# Triple_Socket.net
KiCad netlist of a schematic drawn in EAGLE
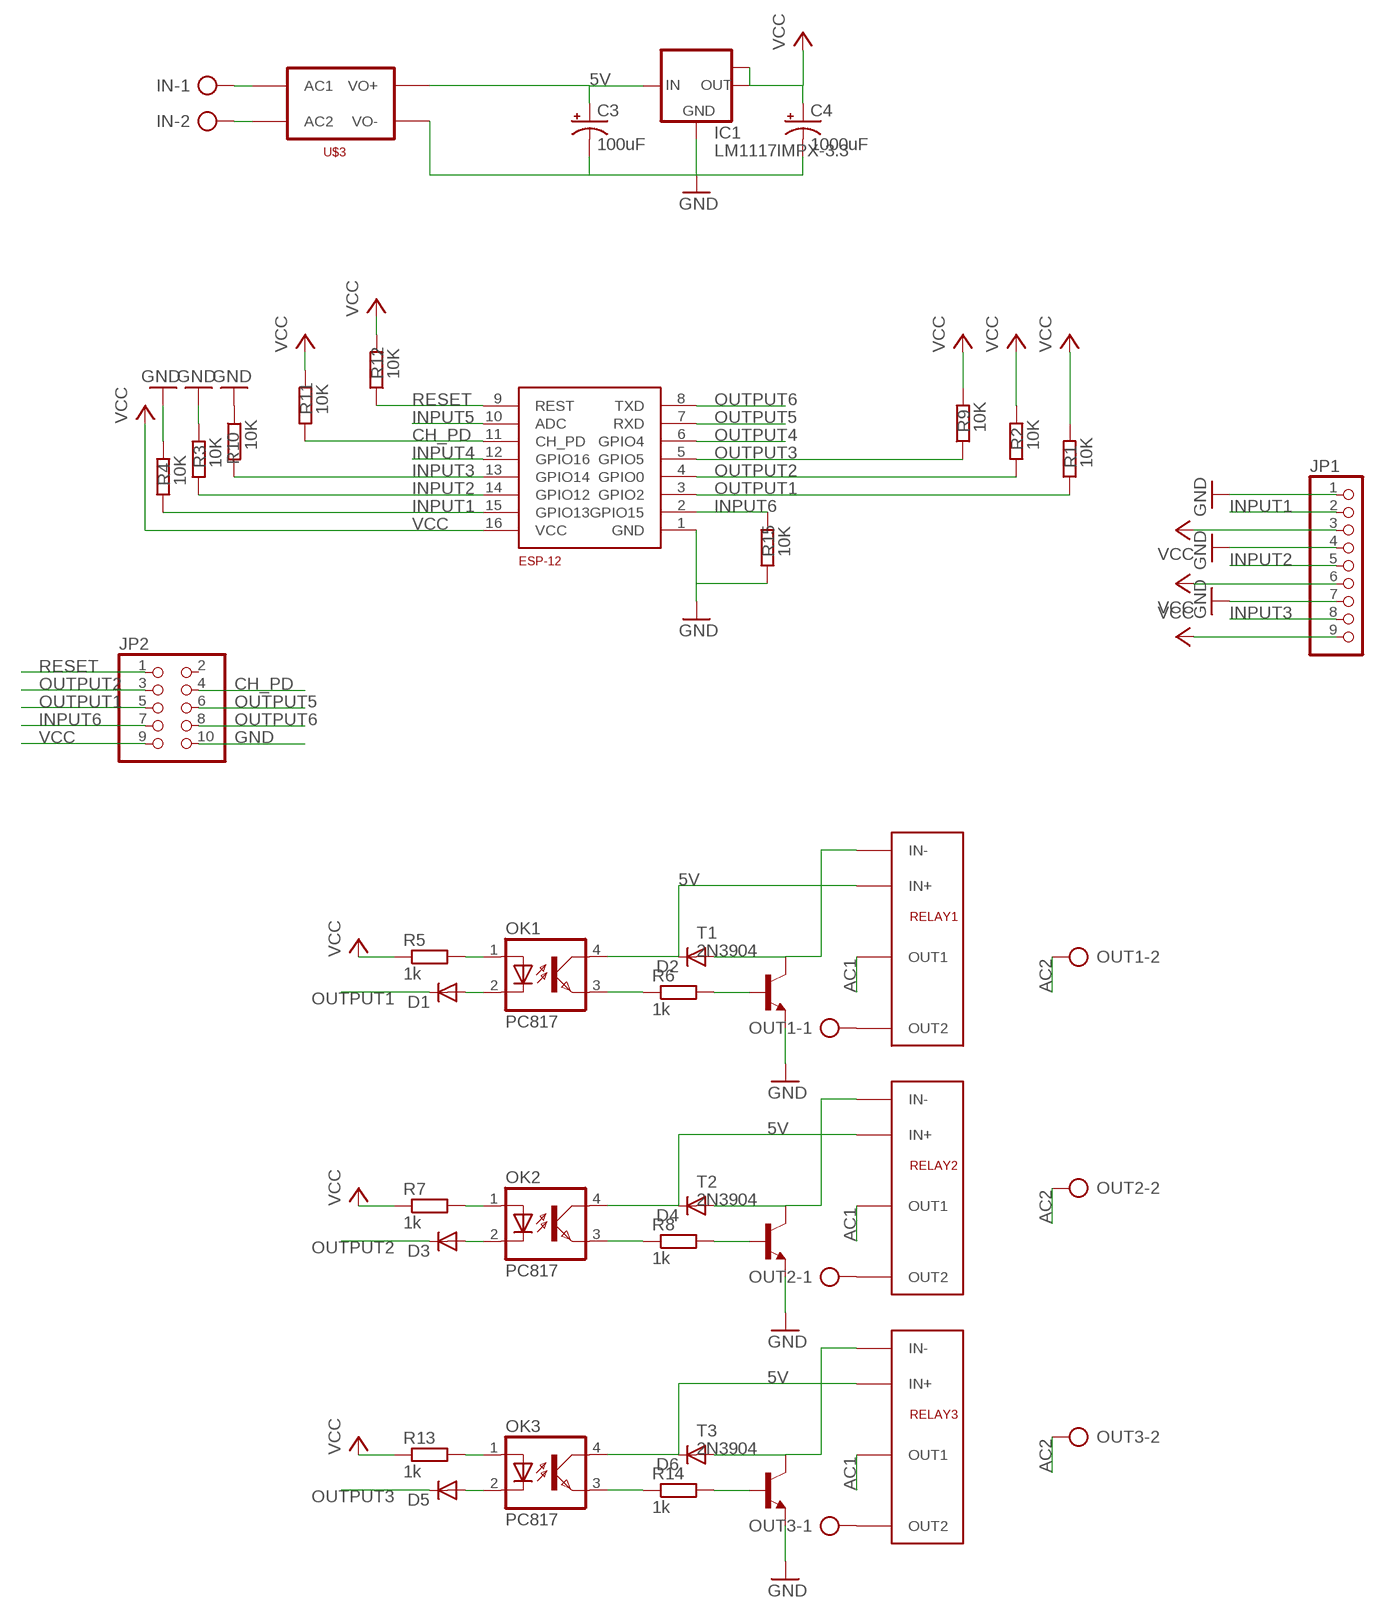
[diagram p0: schematic, sheet 1]

(export (version "E")
  (design (tool "Eeschema 10.0.6"))
  (components
    (comp (ref "C3")
      (value "100uF")
      (footprint "eagle-import:E5-10,5")
      (libsource (lib "eagle-import") (part "CPOL-USE5-10.5"))
    )
    (comp (ref "C4")
      (value "1000uF")
      (footprint "eagle-import:E5-10,5")
      (libsource (lib "eagle-import") (part "CPOL-USE5-10.5"))
    )
    (comp (ref "D1")
      (value "DIODE-SOD80C")
      (footprint "eagle-import:SOD80C")
      (libsource (lib "eagle-import") (part "DIODE-SOD80C"))
    )
    (comp (ref "D2")
      (value "DIODE-SOD80C")
      (footprint "eagle-import:SOD80C")
      (libsource (lib "eagle-import") (part "DIODE-SOD80C"))
    )
    (comp (ref "D3")
      (value "DIODE-SOD80C")
      (footprint "eagle-import:SOD80C")
      (libsource (lib "eagle-import") (part "DIODE-SOD80C"))
    )
    (comp (ref "D4")
      (value "DIODE-SOD80C")
      (footprint "eagle-import:SOD80C")
      (libsource (lib "eagle-import") (part "DIODE-SOD80C"))
    )
    (comp (ref "D5")
      (value "DIODE-SOD80C")
      (footprint "eagle-import:SOD80C")
      (libsource (lib "eagle-import") (part "DIODE-SOD80C"))
    )
    (comp (ref "D6")
      (value "DIODE-SOD80C")
      (footprint "eagle-import:SOD80C")
      (libsource (lib "eagle-import") (part "DIODE-SOD80C"))
    )
    (comp (ref "ESP-12")
      (value "ESP8266_ESP-12")
      (footprint "eagle-import:ESP8266-ESP12")
      (libsource (lib "eagle-import") (part "ESP8266_ESP-12"))
    )
    (comp (ref "IC1")
      (value "LM1117IMPX-3.3")
      (footprint "eagle-import:SOT223")
      (libsource (lib "eagle-import") (part "LM1117IMPX-3.3"))
    )
    (comp (ref "IN")
      (value "AK500/2-H")
      (footprint "eagle-import:AK500_2-H")
      (libsource (lib "eagle-import") (part "AK500/2-H"))
    )
    (comp (ref "JP1")
      (value "PINHD-1X9")
      (footprint "eagle-import:1X09")
      (libsource (lib "eagle-import") (part "PINHD-1X9"))
    )
    (comp (ref "JP2")
      (value "PINHD-2X5")
      (footprint "eagle-import:2X05")
      (libsource (lib "eagle-import") (part "PINHD-2X5"))
    )
    (comp (ref "OK1")
      (value "PC817")
      (footprint "eagle-import:DIL04")
      (fields (field (name "MPN") "PC817X4J000F"))
      (libsource (lib "eagle-import") (part "PC817"))
    )
    (comp (ref "OK2")
      (value "PC817")
      (footprint "eagle-import:DIL04")
      (fields (field (name "MPN") "PC817X4J000F"))
      (libsource (lib "eagle-import") (part "PC817"))
    )
    (comp (ref "OK3")
      (value "PC817")
      (footprint "eagle-import:DIL04")
      (fields (field (name "MPN") "PC817X4J000F"))
      (libsource (lib "eagle-import") (part "PC817"))
    )
    (comp (ref "OUT1")
      (value "AK500/2-H")
      (footprint "eagle-import:AK500_2-H")
      (libsource (lib "eagle-import") (part "AK500/2-H"))
    )
    (comp (ref "OUT2")
      (value "AK500/2-H")
      (footprint "eagle-import:AK500_2-H")
      (libsource (lib "eagle-import") (part "AK500/2-H"))
    )
    (comp (ref "OUT3")
      (value "AK500/2-H")
      (footprint "eagle-import:AK500_2-H")
      (libsource (lib "eagle-import") (part "AK500/2-H"))
    )
    (comp (ref "R1")
      (value "10K")
      (footprint "eagle-import:R0805")
      (libsource (lib "eagle-import") (part "R-EU_R0805"))
    )
    (comp (ref "R2")
      (value "10K")
      (footprint "eagle-import:R0805")
      (libsource (lib "eagle-import") (part "R-EU_R0805"))
    )
    (comp (ref "R3")
      (value "10K")
      (footprint "eagle-import:R0805")
      (libsource (lib "eagle-import") (part "R-EU_R0805"))
    )
    (comp (ref "R4")
      (value "10K")
      (footprint "eagle-import:R0805")
      (libsource (lib "eagle-import") (part "R-EU_R0805"))
    )
    (comp (ref "R5")
      (value "1k")
      (footprint "eagle-import:R0805")
      (libsource (lib "eagle-import") (part "R-EU_R0805"))
    )
    (comp (ref "R6")
      (value "1k")
      (footprint "eagle-import:R0805")
      (libsource (lib "eagle-import") (part "R-EU_R0805"))
    )
    (comp (ref "R7")
      (value "1k")
      (footprint "eagle-import:R0805")
      (libsource (lib "eagle-import") (part "R-EU_R0805"))
    )
    (comp (ref "R8")
      (value "1k")
      (footprint "eagle-import:R0805")
      (libsource (lib "eagle-import") (part "R-EU_R0805"))
    )
    (comp (ref "R9")
      (value "10K")
      (footprint "eagle-import:R0805")
      (libsource (lib "eagle-import") (part "R-EU_R0805"))
    )
    (comp (ref "R10")
      (value "10K")
      (footprint "eagle-import:R0805")
      (libsource (lib "eagle-import") (part "R-EU_R0805"))
    )
    (comp (ref "R11")
      (value "10K")
      (footprint "eagle-import:R0805")
      (libsource (lib "eagle-import") (part "R-EU_R0805"))
    )
    (comp (ref "R12")
      (value "10K")
      (footprint "eagle-import:R0805")
      (libsource (lib "eagle-import") (part "R-EU_R0805"))
    )
    (comp (ref "R13")
      (value "1k")
      (footprint "eagle-import:R0805")
      (libsource (lib "eagle-import") (part "R-EU_R0805"))
    )
    (comp (ref "R14")
      (value "1k")
      (footprint "eagle-import:R0805")
      (libsource (lib "eagle-import") (part "R-EU_R0805"))
    )
    (comp (ref "R15")
      (value "10K")
      (footprint "eagle-import:R0805")
      (libsource (lib "eagle-import") (part "R-EU_R0805"))
    )
    (comp (ref "RELAY1")
      (value "G3MB-202P")
      (footprint "eagle-import:G3MB-202P")
      (libsource (lib "eagle-import") (part "G3MB-202P"))
    )
    (comp (ref "RELAY2")
      (value "G3MB-202P")
      (footprint "eagle-import:G3MB-202P")
      (libsource (lib "eagle-import") (part "G3MB-202P"))
    )
    (comp (ref "RELAY3")
      (value "G3MB-202P")
      (footprint "eagle-import:G3MB-202P")
      (libsource (lib "eagle-import") (part "G3MB-202P"))
    )
    (comp (ref "T1")
      (value "2N3904")
      (footprint "eagle-import:TO92")
      (libsource (lib "eagle-import") (part "2N3904"))
    )
    (comp (ref "T2")
      (value "2N3904")
      (footprint "eagle-import:TO92")
      (libsource (lib "eagle-import") (part "2N3904"))
    )
    (comp (ref "T3")
      (value "2N3904")
      (footprint "eagle-import:TO92")
      (libsource (lib "eagle-import") (part "2N3904"))
    )
    (comp (ref "U$3")
      (value "HLK-PM01")
      (footprint "eagle-import:HLK-PM01")
      (libsource (lib "eagle-import") (part "HLK-PM01"))
    )
  )
  (nets
    (net (code "1") (name "/5V") (class "Default")
      (node (ref "C3") (pin "+") (pinfunction "+_+") (pintype "passive"))
      (node (ref "D2") (pin "C") (pinfunction "C_C") (pintype "passive"))
      (node (ref "D4") (pin "C") (pinfunction "C_C") (pintype "passive"))
      (node (ref "D6") (pin "C") (pinfunction "C_C") (pintype "passive"))
      (node (ref "IC1") (pin "3") (pinfunction "IN_3") (pintype "input"))
      (node (ref "OK1") (pin "4") (pinfunction "COL_4") (pintype "passive"))
      (node (ref "OK2") (pin "4") (pinfunction "COL_4") (pintype "passive"))
      (node (ref "OK3") (pin "4") (pinfunction "COL_4") (pintype "passive"))
      (node (ref "RELAY1") (pin "IN+") (pinfunction "IN+_IN+") (pintype "bidirectional"))
      (node (ref "RELAY2") (pin "IN+") (pinfunction "IN+_IN+") (pintype "bidirectional"))
      (node (ref "RELAY3") (pin "IN+") (pinfunction "IN+_IN+") (pintype "bidirectional"))
      (node (ref "U$3") (pin "VO+") (pinfunction "VO+_VO+") (pintype "bidirectional"))
    )
    (net (code "2") (name "/AC1") (class "Default")
      (node (ref "IN") (pin "1") (pinfunction "KL_1") (pintype "passive"))
      (node (ref "RELAY1") (pin "OUT1") (pinfunction "OUT1_OUT1") (pintype "bidirectional"))
      (node (ref "RELAY2") (pin "OUT1") (pinfunction "OUT1_OUT1") (pintype "bidirectional"))
      (node (ref "RELAY3") (pin "OUT1") (pinfunction "OUT1_OUT1") (pintype "bidirectional"))
      (node (ref "U$3") (pin "AC1") (pinfunction "AC1_AC1") (pintype "bidirectional"))
    )
    (net (code "3") (name "/AC2") (class "Default")
      (node (ref "IN") (pin "2") (pinfunction "KL_2") (pintype "passive"))
      (node (ref "OUT1") (pin "2") (pinfunction "KL_2") (pintype "passive"))
      (node (ref "OUT2") (pin "2") (pinfunction "KL_2") (pintype "passive"))
      (node (ref "OUT3") (pin "2") (pinfunction "KL_2") (pintype "passive"))
      (node (ref "U$3") (pin "AC2") (pinfunction "AC2_AC2") (pintype "bidirectional"))
    )
    (net (code "4") (name "/CH_PD") (class "Default")
      (node (ref "ESP-12") (pin "11") (pinfunction "CH_PD_11") (pintype "bidirectional"))
      (node (ref "JP2") (pin "4") (pinfunction "4_4") (pintype "passive"))
      (node (ref "R11") (pin "1") (pinfunction "1_1") (pintype "passive"))
    )
    (net (code "5") (name "/INPUT1") (class "Default")
      (node (ref "ESP-12") (pin "15") (pinfunction "GPIO13_15") (pintype "bidirectional"))
      (node (ref "JP1") (pin "2") (pinfunction "2_2") (pintype "passive"))
      (node (ref "R4") (pin "1") (pinfunction "1_1") (pintype "passive"))
    )
    (net (code "6") (name "/INPUT2") (class "Default")
      (node (ref "ESP-12") (pin "14") (pinfunction "GPIO12_14") (pintype "bidirectional"))
      (node (ref "JP1") (pin "5") (pinfunction "5_5") (pintype "passive"))
      (node (ref "R3") (pin "2") (pinfunction "2_2") (pintype "passive"))
    )
    (net (code "7") (name "/INPUT3") (class "Default")
      (node (ref "ESP-12") (pin "13") (pinfunction "GPIO14_13") (pintype "bidirectional"))
      (node (ref "JP1") (pin "8") (pinfunction "8_8") (pintype "passive"))
      (node (ref "R10") (pin "2") (pinfunction "2_2") (pintype "passive"))
    )
    (net (code "8") (name "/INPUT4") (class "Default")
      (node (ref "ESP-12") (pin "12") (pinfunction "GPIO16_12") (pintype "bidirectional"))
    )
    (net (code "9") (name "/INPUT5") (class "Default")
      (node (ref "ESP-12") (pin "10") (pinfunction "ADC_10") (pintype "bidirectional"))
    )
    (net (code "10") (name "/INPUT6") (class "Default")
      (node (ref "ESP-12") (pin "2") (pinfunction "GPIO15_2") (pintype "bidirectional"))
      (node (ref "JP2") (pin "7") (pinfunction "7_7") (pintype "passive"))
      (node (ref "R15") (pin "2") (pinfunction "2_2") (pintype "passive"))
    )
    (net (code "11") (name "/OUTPUT1") (class "Default")
      (node (ref "D1") (pin "C") (pinfunction "C_C") (pintype "passive"))
      (node (ref "ESP-12") (pin "3") (pinfunction "GPIO2_3") (pintype "bidirectional"))
      (node (ref "JP2") (pin "5") (pinfunction "5_5") (pintype "passive"))
      (node (ref "R1") (pin "1") (pinfunction "1_1") (pintype "passive"))
    )
    (net (code "12") (name "/OUTPUT2") (class "Default")
      (node (ref "D3") (pin "C") (pinfunction "C_C") (pintype "passive"))
      (node (ref "ESP-12") (pin "4") (pinfunction "GPIO0_4") (pintype "bidirectional"))
      (node (ref "JP2") (pin "3") (pinfunction "3_3") (pintype "passive"))
      (node (ref "R2") (pin "1") (pinfunction "1_1") (pintype "passive"))
    )
    (net (code "13") (name "/OUTPUT3") (class "Default")
      (node (ref "D5") (pin "C") (pinfunction "C_C") (pintype "passive"))
      (node (ref "ESP-12") (pin "5") (pinfunction "GPIO5_5") (pintype "bidirectional"))
      (node (ref "R9") (pin "1") (pinfunction "1_1") (pintype "passive"))
    )
    (net (code "14") (name "/OUTPUT4") (class "Default")
      (node (ref "ESP-12") (pin "6") (pinfunction "GPIO4_6") (pintype "bidirectional"))
    )
    (net (code "15") (name "/OUTPUT5") (class "Default")
      (node (ref "ESP-12") (pin "7") (pinfunction "RXD_7") (pintype "bidirectional"))
      (node (ref "JP2") (pin "6") (pinfunction "6_6") (pintype "passive"))
    )
    (net (code "16") (name "/OUTPUT6") (class "Default")
      (node (ref "ESP-12") (pin "8") (pinfunction "TXD_8") (pintype "bidirectional"))
      (node (ref "JP2") (pin "8") (pinfunction "8_8") (pintype "passive"))
    )
    (net (code "17") (name "/RESET") (class "Default")
      (node (ref "ESP-12") (pin "9") (pinfunction "REST_9") (pintype "bidirectional"))
      (node (ref "JP2") (pin "1") (pinfunction "1_1") (pintype "passive"))
      (node (ref "R12") (pin "1") (pinfunction "1_1") (pintype "passive"))
    )
    (net (code "18") (name "GND") (class "Default")
      (node (ref "C3") (pin "-") (pinfunction "-_-") (pintype "passive"))
      (node (ref "C4") (pin "-") (pinfunction "-_-") (pintype "passive"))
      (node (ref "ESP-12") (pin "1") (pinfunction "GND_1") (pintype "bidirectional"))
      (node (ref "IC1") (pin "1") (pinfunction "GND_1") (pintype "input"))
      (node (ref "JP1") (pin "1") (pinfunction "1_1") (pintype "passive"))
      (node (ref "JP1") (pin "4") (pinfunction "4_4") (pintype "passive"))
      (node (ref "JP1") (pin "7") (pinfunction "7_7") (pintype "passive"))
      (node (ref "JP2") (pin "10") (pinfunction "10_10") (pintype "passive"))
      (node (ref "R10") (pin "1") (pinfunction "1_1") (pintype "passive"))
      (node (ref "R15") (pin "1") (pinfunction "1_1") (pintype "passive"))
      (node (ref "R3") (pin "1") (pinfunction "1_1") (pintype "passive"))
      (node (ref "R4") (pin "2") (pinfunction "2_2") (pintype "passive"))
      (node (ref "T1") (pin "3") (pinfunction "E_3") (pintype "passive"))
      (node (ref "T2") (pin "3") (pinfunction "E_3") (pintype "passive"))
      (node (ref "T3") (pin "3") (pinfunction "E_3") (pintype "passive"))
      (node (ref "U$3") (pin "VO-") (pinfunction "VO-_VO-") (pintype "bidirectional"))
    )
    (net (code "19") (name "Net-(OK1-A)") (class "Default")
      (node (ref "OK1") (pin "1") (pinfunction "A_1") (pintype "passive"))
      (node (ref "R5") (pin "2") (pinfunction "2_2") (pintype "passive"))
    )
    (net (code "20") (name "Net-(OK1-C)") (class "Default")
      (node (ref "D1") (pin "A") (pinfunction "A_A") (pintype "passive"))
      (node (ref "OK1") (pin "2") (pinfunction "C_2") (pintype "passive"))
    )
    (net (code "21") (name "Net-(OK1-EMIT)") (class "Default")
      (node (ref "OK1") (pin "3") (pinfunction "EMIT_3") (pintype "passive"))
      (node (ref "R6") (pin "1") (pinfunction "1_1") (pintype "passive"))
    )
    (net (code "22") (name "Net-(OK2-A)") (class "Default")
      (node (ref "OK2") (pin "1") (pinfunction "A_1") (pintype "passive"))
      (node (ref "R7") (pin "2") (pinfunction "2_2") (pintype "passive"))
    )
    (net (code "23") (name "Net-(OK2-C)") (class "Default")
      (node (ref "D3") (pin "A") (pinfunction "A_A") (pintype "passive"))
      (node (ref "OK2") (pin "2") (pinfunction "C_2") (pintype "passive"))
    )
    (net (code "24") (name "Net-(OK2-EMIT)") (class "Default")
      (node (ref "OK2") (pin "3") (pinfunction "EMIT_3") (pintype "passive"))
      (node (ref "R8") (pin "1") (pinfunction "1_1") (pintype "passive"))
    )
    (net (code "25") (name "Net-(OK3-A)") (class "Default")
      (node (ref "OK3") (pin "1") (pinfunction "A_1") (pintype "passive"))
      (node (ref "R13") (pin "2") (pinfunction "2_2") (pintype "passive"))
    )
    (net (code "26") (name "Net-(OK3-C)") (class "Default")
      (node (ref "D5") (pin "A") (pinfunction "A_A") (pintype "passive"))
      (node (ref "OK3") (pin "2") (pinfunction "C_2") (pintype "passive"))
    )
    (net (code "27") (name "Net-(OK3-EMIT)") (class "Default")
      (node (ref "OK3") (pin "3") (pinfunction "EMIT_3") (pintype "passive"))
      (node (ref "R14") (pin "1") (pinfunction "1_1") (pintype "passive"))
    )
    (net (code "28") (name "Net-(OUT1A-KL)") (class "Default")
      (node (ref "OUT1") (pin "1") (pinfunction "KL_1") (pintype "passive"))
      (node (ref "RELAY1") (pin "OUT2") (pinfunction "OUT2_OUT2") (pintype "bidirectional"))
    )
    (net (code "29") (name "Net-(OUT2A-KL)") (class "Default")
      (node (ref "OUT2") (pin "1") (pinfunction "KL_1") (pintype "passive"))
      (node (ref "RELAY2") (pin "OUT2") (pinfunction "OUT2_OUT2") (pintype "bidirectional"))
    )
    (net (code "30") (name "Net-(OUT3A-KL)") (class "Default")
      (node (ref "OUT3") (pin "1") (pinfunction "KL_1") (pintype "passive"))
      (node (ref "RELAY3") (pin "OUT2") (pinfunction "OUT2_OUT2") (pintype "bidirectional"))
    )
    (net (code "31") (name "Net-(T1-B)") (class "Default")
      (node (ref "R6") (pin "2") (pinfunction "2_2") (pintype "passive"))
      (node (ref "T1") (pin "2") (pinfunction "B_2") (pintype "passive"))
    )
    (net (code "32") (name "Net-(T1-C)") (class "Default")
      (node (ref "D2") (pin "A") (pinfunction "A_A") (pintype "passive"))
      (node (ref "RELAY1") (pin "IN-") (pinfunction "IN-_IN-") (pintype "bidirectional"))
      (node (ref "T1") (pin "1") (pinfunction "C_1") (pintype "passive"))
    )
    (net (code "33") (name "Net-(T2-B)") (class "Default")
      (node (ref "R8") (pin "2") (pinfunction "2_2") (pintype "passive"))
      (node (ref "T2") (pin "2") (pinfunction "B_2") (pintype "passive"))
    )
    (net (code "34") (name "Net-(T2-C)") (class "Default")
      (node (ref "D4") (pin "A") (pinfunction "A_A") (pintype "passive"))
      (node (ref "RELAY2") (pin "IN-") (pinfunction "IN-_IN-") (pintype "bidirectional"))
      (node (ref "T2") (pin "1") (pinfunction "C_1") (pintype "passive"))
    )
    (net (code "35") (name "Net-(T3-B)") (class "Default")
      (node (ref "R14") (pin "2") (pinfunction "2_2") (pintype "passive"))
      (node (ref "T3") (pin "2") (pinfunction "B_2") (pintype "passive"))
    )
    (net (code "36") (name "Net-(T3-C)") (class "Default")
      (node (ref "D6") (pin "A") (pinfunction "A_A") (pintype "passive"))
      (node (ref "RELAY3") (pin "IN-") (pinfunction "IN-_IN-") (pintype "bidirectional"))
      (node (ref "T3") (pin "1") (pinfunction "C_1") (pintype "passive"))
    )
    (net (code "37") (name "VCC") (class "Default")
      (node (ref "C4") (pin "+") (pinfunction "+_+") (pintype "passive"))
      (node (ref "ESP-12") (pin "16") (pinfunction "VCC_16") (pintype "bidirectional"))
      (node (ref "IC1") (pin "2") (pinfunction "OUT_2") (pintype "passive"))
      (node (ref "IC1") (pin "TAB") (pinfunction "OUT1_TAB") (pintype "passive"))
      (node (ref "JP1") (pin "3") (pinfunction "3_3") (pintype "passive"))
      (node (ref "JP1") (pin "6") (pinfunction "6_6") (pintype "passive"))
      (node (ref "JP1") (pin "9") (pinfunction "9_9") (pintype "passive"))
      (node (ref "JP2") (pin "9") (pinfunction "9_9") (pintype "passive"))
      (node (ref "R1") (pin "2") (pinfunction "2_2") (pintype "passive"))
      (node (ref "R11") (pin "2") (pinfunction "2_2") (pintype "passive"))
      (node (ref "R12") (pin "2") (pinfunction "2_2") (pintype "passive"))
      (node (ref "R13") (pin "1") (pinfunction "1_1") (pintype "passive"))
      (node (ref "R2") (pin "2") (pinfunction "2_2") (pintype "passive"))
      (node (ref "R5") (pin "1") (pinfunction "1_1") (pintype "passive"))
      (node (ref "R7") (pin "1") (pinfunction "1_1") (pintype "passive"))
      (node (ref "R9") (pin "2") (pinfunction "2_2") (pintype "passive"))
    )
    (net (code "38") (name "unconnected-(JP2-Pad2)") (class "Default")
      (node (ref "JP2") (pin "2") (pinfunction "2_2") (pintype "passive"))
    )
  )
)
